# Master.net
KiCad netlist of a schematic drawn in Altium Designer
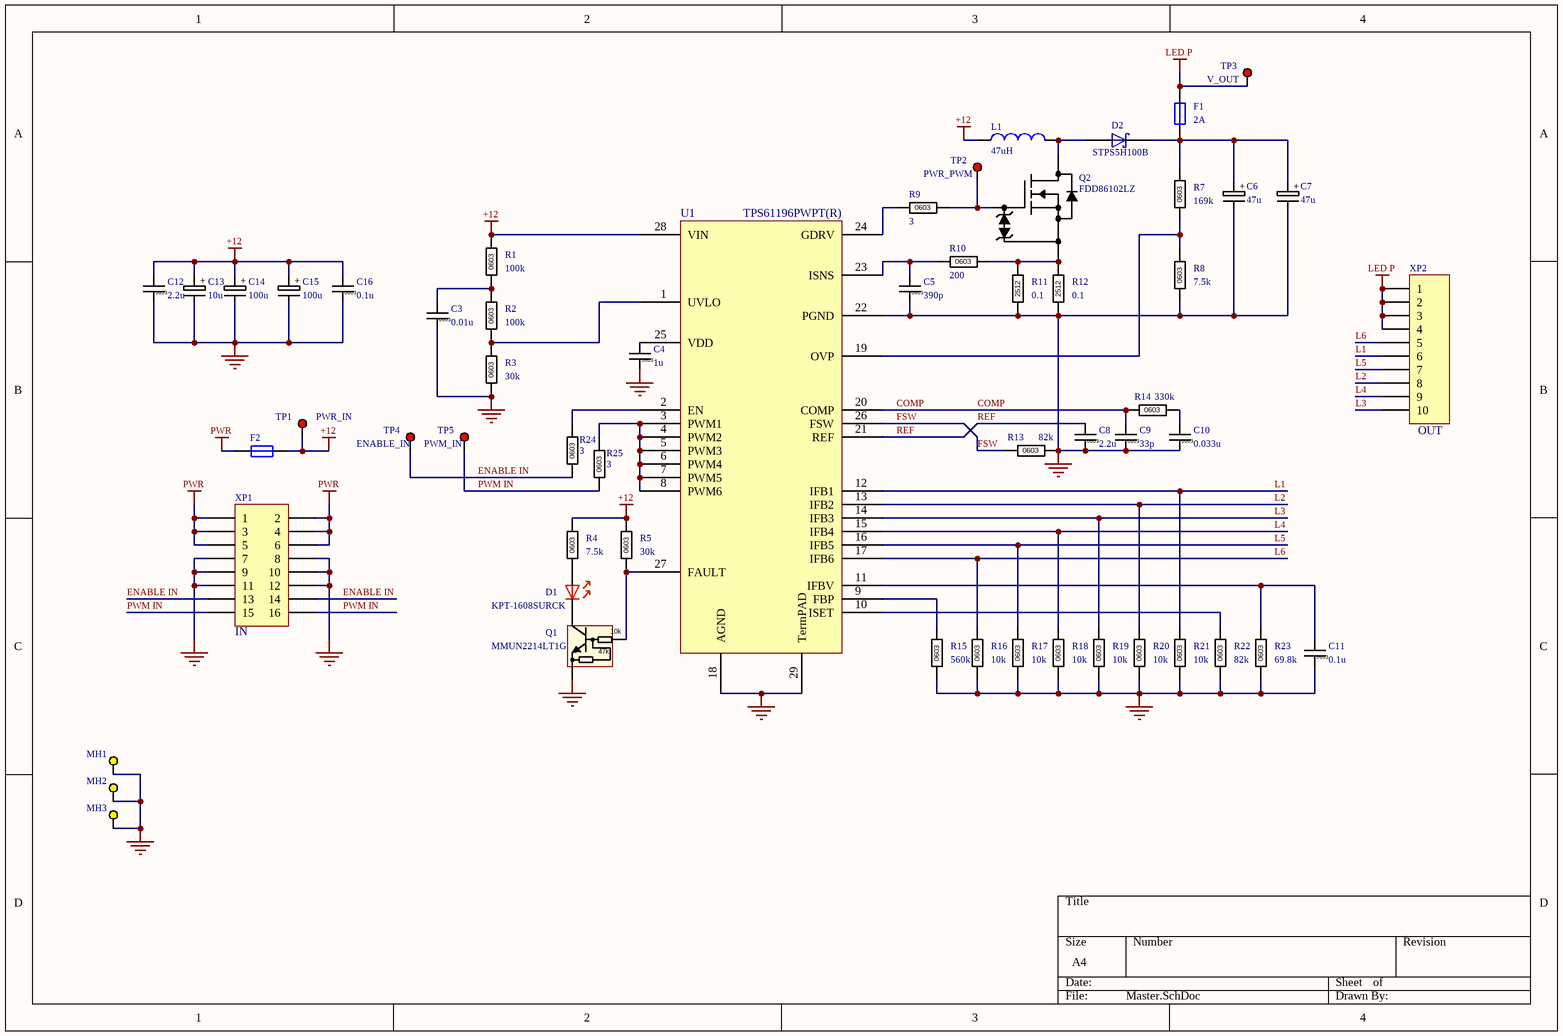
[diagram p0: Master.SchDoc]

(export (version "E")
  (design (tool "Eeschema 10.0.6"))
  (components
    (comp (ref "C3")
      (value "0603-X7R-50-0.01 мкф")
      (footprint "CAP_0603")
      (description "Конденсатор Чип Керамический")
      (fields (field (name "VOLTAGE") "50V") (field (name "CAP") "0.01u") (field (name "FOOT") "0603"))
      (libsource (lib "main") (part "0603-X7R-50-0.01 мкф"))
    )
    (comp (ref "C4")
      (value "0603-X5R-10 1 мкф")
      (footprint "CAP_0603")
      (description "Конденсатор Чип Керамический")
      (fields (field (name "VOLTAGE") "10V") (field (name "CAP") "1u") (field (name "FOOT") "0603"))
      (libsource (lib "main") (part "0603-X5R-10 1 мкф"))
    )
    (comp (ref "C5")
      (value "0603-NP0-50-390 пф J")
      (footprint "CAP_0603")
      (description "Конденсатор Чип Керамический")
      (fields (field (name "VOLTAGE") "50V") (field (name "CAP") "390p") (field (name "FOOT") "0603"))
      (libsource (lib "main") (part "0603-NP0-50-390 пф J"))
    )
    (comp (ref "C6")
      (value "ECAP 47uF 100V 10x12.5")
      (footprint "CAP_ECR 10X12.5")
      (fields (field (name "VOLTAGE") "100V") (field (name "CAP") "47u"))
      (libsource (lib "main") (part "ECAP 47uF 100V 10x12.5"))
    )
    (comp (ref "C7")
      (value "ECAP 47uF 100V 10x12.5")
      (footprint "CAP_ECR 10X12.5")
      (fields (field (name "VOLTAGE") "100V") (field (name "CAP") "47u"))
      (libsource (lib "main") (part "ECAP 47uF 100V 10x12.5"))
    )
    (comp (ref "C8")
      (value "0603-X7R-10 2.2 мкф")
      (footprint "CAP_0603")
      (description "Конденсатор Чип Керамический")
      (fields (field (name "VOLTAGE") "10V") (field (name "CAP") "2.2u") (field (name "FOOT") "0603"))
      (libsource (lib "main") (part "0603-X7R-10 2.2 мкф"))
    )
    (comp (ref "C9")
      (value "0603-NP0-50-33 пф J")
      (footprint "CAP_0603")
      (description "Конденсатор Чип Керамический")
      (fields (field (name "VOLTAGE") "50V") (field (name "CAP") "33p") (field (name "FOOT") "0603"))
      (libsource (lib "main") (part "0603-NP0-50-33 пф J"))
    )
    (comp (ref "C10")
      (value "0603-X7R-50-0.033 мкф")
      (footprint "CAP_0603")
      (description "Конденсатор Чип Керамический")
      (fields (field (name "VOLTAGE") "50V") (field (name "CAP") "0.033u") (field (name "FOOT") "0603"))
      (libsource (lib "main") (part "0603-X7R-50-0.033 мкф"))
    )
    (comp (ref "C11")
      (value "0603-X7R-50-0.1 мкф")
      (footprint "CAP_0603")
      (description "Конденсатор Чип Керамический")
      (fields (field (name "VOLTAGE") "50V") (field (name "CAP") "0.1u") (field (name "FOOT") "0603"))
      (libsource (lib "main") (part "0603-X7R-50-0.1 мкф"))
    )
    (comp (ref "C12")
      (value "0603-X7R-10 2.2 мкф")
      (footprint "CAP_0603")
      (description "Конденсатор Чип Керамический")
      (fields (field (name "VOLTAGE") "10V") (field (name "CAP") "2.2u") (field (name "FOOT") "0603"))
      (libsource (lib "main") (part "0603-X7R-10 2.2 мкф"))
    )
    (comp (ref "C13")
      (value "ESX 50 в-10 мкф 5x11 Hitano")
      (footprint "CAP_ECR 5X11")
      (description "Конденсатор Алюминиевый Низкоимпедансный")
      (fields (field (name "VOLTAGE") "50V") (field (name "CAP") "10u"))
      (libsource (lib "main") (part "ESX 50 в-10 мкф 5x11 Hitano"))
    )
    (comp (ref "C14")
      (value "ECAP (К50-35), 100мкФ, 35В, 105°C, 20%, 6.3x12мм P:2.5мм")
      (footprint "CAP_ECR 5X11")
      (description "Конденсатор электролитический алюминиевый")
      (fields (field (name "VOLTAGE") "50V") (field (name "CAP") "100u"))
      (libsource (lib "main") (part "ECAP 50V 100uF 6.3x12"))
    )
    (comp (ref "C15")
      (value "ECAP (К50-35), 100мкФ, 35В, 105°C, 20%, 6.3x12мм P:2.5мм")
      (footprint "CAP_ECR 5X11")
      (description "Конденсатор электролитический алюминиевый")
      (fields (field (name "VOLTAGE") "50V") (field (name "CAP") "100u"))
      (libsource (lib "main") (part "ECAP 50V 100uF 6.3x12"))
    )
    (comp (ref "C16")
      (value "0603-X7R-50-0.1 мкф")
      (footprint "CAP_0603")
      (description "Конденсатор Чип Керамический")
      (fields (field (name "VOLTAGE") "50V") (field (name "CAP") "0.1u") (field (name "FOOT") "0603"))
      (libsource (lib "main") (part "0603-X7R-50-0.1 мкф"))
    )
    (comp (ref "D1")
      (value "KPT-1608SURCK")
      (footprint "LED_0603_RED")
      (fields
        (field (name "Comment") "KPT-1608SURCK, KingBright")
        (field (name "HELPURL") "L:\\Dev\\Техническая документация\\Светодиоды\\Kingbright\\SMD\\KPT-1608SURCK(0603).pdf")
      )
      (libsource (lib "main") (part "LED_0603_KPT-1608SURCK_red_120mcd"))
    )
    (comp (ref "D2")
      (value "STPS5H100B")
      (footprint "D-PAK")
      (description "DIODE SCHOTTKY 5A 100V")
      (libsource (lib "main") (part "Schottky_STPS5H100B"))
    )
    (comp (ref "F1")
      (value "2A")
      (footprint "FUSE_LITTEL_0154")
      (description "Плавкий предохранитель LITTELFUSE 0154")
      (libsource (lib "main") (part "FUSE_LITTEL 0154"))
    )
    (comp (ref "F2")
      (value "~")
      (footprint "FUSE_LITTEL_0154")
      (description "Плавкий предохранитель LITTELFUSE 0154")
      (libsource (lib "main") (part "FUSE_LITTEL 0154"))
    )
    (comp (ref "L1")
      (value "47uH")
      (footprint "INDUCTOR_B82477G")
      (description "47 мкГн, 2.5 А, 12.8х12.8, Катушка индуктивности SMD")
      (libsource (lib "main") (part "INDUCTOR_B82477G4473M"))
    )
    (comp (ref "MH1")
      (value "MOUNTING HOLE 3MM")
      (footprint "MOUNTING HOLE 3MM")
      (libsource (lib "main") (part "MOUNTING HOLE 3MM"))
    )
    (comp (ref "MH2")
      (value "MOUNTING HOLE 3MM")
      (footprint "MOUNTING HOLE 3MM")
      (libsource (lib "main") (part "MOUNTING HOLE 3MM"))
    )
    (comp (ref "MH3")
      (value "MOUNTING HOLE 3MM")
      (footprint "MOUNTING HOLE 3MM")
      (libsource (lib "main") (part "MOUNTING HOLE 3MM"))
    )
    (comp (ref "Q1")
      (value "MMUN2214LT1G")
      (footprint "SOT_23")
      (description "NPN Digital Transistor")
      (fields (field (name "PUBLISHER") "Altium Limited"))
      (libsource (lib "main") (part "BEC_MMUN2214LT1G_50V 0.1A 0.25W"))
    )
    (comp (ref "Q2")
      (value "FDD86102LZ")
      (footprint "D-PAK")
      (description "MOSFET N-CHANNEL 100V 8A")
      (libsource (lib "main") (part "MOSFET_FDD86102LZ"))
    )
    (comp (ref "R1")
      (value "100k")
      (footprint "resistor_0603")
      (description "Резистор Чип")
      (fields
        (field (name "POWER") "0.1W")
        (field (name "FOOT") "0603")
        (field (name "Comment") "0603-100к J")
      )
      (libsource (lib "main") (part "0603-100 к J"))
    )
    (comp (ref "R2")
      (value "100k")
      (footprint "resistor_0603")
      (description "Резистор Чип")
      (fields
        (field (name "POWER") "0.1W")
        (field (name "FOOT") "0603")
        (field (name "Comment") "0603-100к J")
      )
      (libsource (lib "main") (part "0603-100 к J"))
    )
    (comp (ref "R3")
      (value "30k")
      (footprint "resistor_0603")
      (description "Резистор Чип")
      (fields (field (name "POWER") "0.1W") (field (name "TOLERANCE") "1%") (field (name "FOOT") "0603"))
      (libsource (lib "main") (part "0603-30 к F"))
    )
    (comp (ref "R4")
      (value "7.5k")
      (footprint "resistor_0603")
      (description "Резистор Чип")
      (fields (field (name "POWER") "0.1W") (field (name "TOLERANCE") "1%") (field (name "FOOT") "0603"))
      (libsource (lib "main") (part "0603-7.5 к F"))
    )
    (comp (ref "R5")
      (value "30k")
      (footprint "resistor_0603")
      (description "Резистор Чип")
      (fields (field (name "POWER") "0.1W") (field (name "TOLERANCE") "1%") (field (name "FOOT") "0603"))
      (libsource (lib "main") (part "0603-30 к F"))
    )
    (comp (ref "R7")
      (value "169k")
      (footprint "resistor_0603")
      (description "Резистор Чип")
      (fields (field (name "POWER") "0.1W") (field (name "TOLERANCE") "1%") (field (name "FOOT") "0603"))
      (libsource (lib "main") (part "0603-169 к F"))
    )
    (comp (ref "R8")
      (value "7.5k")
      (footprint "resistor_0603")
      (description "Резистор Чип")
      (fields (field (name "POWER") "0.1W") (field (name "TOLERANCE") "1%") (field (name "FOOT") "0603"))
      (libsource (lib "main") (part "0603-7.5 к F"))
    )
    (comp (ref "R9")
      (value "3")
      (footprint "resistor_0603")
      (description "Резистор Чип")
      (fields (field (name "POWER") "0.1W") (field (name "TOLERANCE") "1%") (field (name "FOOT") "0603"))
      (libsource (lib "main") (part "0603-3 F"))
    )
    (comp (ref "R10")
      (value "200")
      (footprint "resistor_0603")
      (description "Резистор Чип")
      (fields (field (name "POWER") "0.1W") (field (name "TOLERANCE") "1%") (field (name "FOOT") "0603"))
      (libsource (lib "main") (part "0603-200 F"))
    )
    (comp (ref "R11")
      (value "0.1")
      (footprint "resistor_2512")
      (description "Резистор Чип")
      (fields (field (name "POWER") "1W") (field (name "FOOT") "2512") (field (name "Comment") "2512-0.1 F"))
      (libsource (lib "main") (part "2512-0.1 F"))
    )
    (comp (ref "R12")
      (value "0.1")
      (footprint "resistor_2512")
      (description "Резистор Чип")
      (fields (field (name "POWER") "1W") (field (name "FOOT") "2512") (field (name "Comment") "2512-0.1 F"))
      (libsource (lib "main") (part "2512-0.1 F"))
    )
    (comp (ref "R13")
      (value "82k")
      (footprint "resistor_0603")
      (description "Резистор Чип")
      (fields
        (field (name "POWER") "0.1W")
        (field (name "FOOT") "0603")
        (field (name "Comment") "0603-82 к J")
      )
      (libsource (lib "main") (part "0603-82 к J"))
    )
    (comp (ref "R14")
      (value "330k")
      (footprint "resistor_0603")
      (description "Резистор Чип")
      (fields
        (field (name "POWER") "0.1W")
        (field (name "FOOT") "0603")
        (field (name "Comment") "0603-330 J")
      )
      (libsource (lib "main") (part "0603-330 J"))
    )
    (comp (ref "R15")
      (value "560k")
      (footprint "resistor_0603")
      (description "Резистор Чип")
      (fields (field (name "POWER") "0.1W") (field (name "TOLERANCE") "1%") (field (name "FOOT") "0603"))
      (libsource (lib "main") (part "0603-560 к F"))
    )
    (comp (ref "R16")
      (value "10k")
      (footprint "resistor_0603")
      (description "Резистор Чип")
      (fields
        (field (name "POWER") "0.1W")
        (field (name "FOOT") "0603")
        (field (name "Comment") "0603-10к J")
      )
      (libsource (lib "main") (part "0603-10 к J"))
    )
    (comp (ref "R17")
      (value "10k")
      (footprint "resistor_0603")
      (description "Резистор Чип")
      (fields
        (field (name "POWER") "0.1W")
        (field (name "FOOT") "0603")
        (field (name "Comment") "0603-10к J")
      )
      (libsource (lib "main") (part "0603-10 к J"))
    )
    (comp (ref "R18")
      (value "10k")
      (footprint "resistor_0603")
      (description "Резистор Чип")
      (fields
        (field (name "POWER") "0.1W")
        (field (name "FOOT") "0603")
        (field (name "Comment") "0603-10к J")
      )
      (libsource (lib "main") (part "0603-10 к J"))
    )
    (comp (ref "R19")
      (value "10k")
      (footprint "resistor_0603")
      (description "Резистор Чип")
      (fields
        (field (name "POWER") "0.1W")
        (field (name "FOOT") "0603")
        (field (name "Comment") "0603-10к J")
      )
      (libsource (lib "main") (part "0603-10 к J"))
    )
    (comp (ref "R20")
      (value "10k")
      (footprint "resistor_0603")
      (description "Резистор Чип")
      (fields
        (field (name "POWER") "0.1W")
        (field (name "FOOT") "0603")
        (field (name "Comment") "0603-10к J")
      )
      (libsource (lib "main") (part "0603-10 к J"))
    )
    (comp (ref "R21")
      (value "10k")
      (footprint "resistor_0603")
      (description "Резистор Чип")
      (fields
        (field (name "POWER") "0.1W")
        (field (name "FOOT") "0603")
        (field (name "Comment") "0603-10к J")
      )
      (libsource (lib "main") (part "0603-10 к J"))
    )
    (comp (ref "R22")
      (value "82k")
      (footprint "resistor_0603")
      (description "Резистор Чип")
      (fields
        (field (name "POWER") "0.1W")
        (field (name "FOOT") "0603")
        (field (name "Comment") "0603-82 к J")
      )
      (libsource (lib "main") (part "0603-82 к J"))
    )
    (comp (ref "R23")
      (value "69.8k")
      (footprint "resistor_0603")
      (description "Резистор Чип")
      (fields (field (name "POWER") "0.1W") (field (name "TOLERANCE") "1%") (field (name "FOOT") "0603"))
      (libsource (lib "main") (part "0603-69.8 к F"))
    )
    (comp (ref "R24")
      (value "3")
      (footprint "resistor_0603")
      (description "Резистор Чип")
      (fields (field (name "POWER") "0.1W") (field (name "TOLERANCE") "1%") (field (name "FOOT") "0603"))
      (libsource (lib "main") (part "0603-3 F"))
    )
    (comp (ref "R25")
      (value "3")
      (footprint "resistor_0603")
      (description "Резистор Чип")
      (fields (field (name "POWER") "0.1W") (field (name "TOLERANCE") "1%") (field (name "FOOT") "0603"))
      (libsource (lib "main") (part "0603-3 F"))
    )
    (comp (ref "TP1")
      (value "PWR_IN")
      (footprint "OTHER_SMD_TP_1.5MM")
      (libsource (lib "main") (part "Test Point_1.5MM"))
    )
    (comp (ref "TP2")
      (value "PWR_PWM")
      (footprint "OTHER_SMD_TP_1.5MM")
      (libsource (lib "main") (part "Test Point_1.5MM"))
    )
    (comp (ref "TP3")
      (value "V_OUT")
      (footprint "OTHER_SMD_TP_1.5MM")
      (libsource (lib "main") (part "Test Point_1.5MM"))
    )
    (comp (ref "TP4")
      (value "ENABLE_IN")
      (footprint "OTHER_SMD_TP_1.5MM")
      (libsource (lib "main") (part "Test Point_1.5MM"))
    )
    (comp (ref "TP5")
      (value "PWM_IN")
      (footprint "OTHER_SMD_TP_1.5MM")
      (libsource (lib "main") (part "Test Point_1.5MM"))
    )
    (comp (ref "U1")
      (value "TPS61196PWPT(R)")
      (footprint "HTSSOP_28")
      (libsource (lib "main") (part "LED DRV_TPS61196"))
    )
    (comp (ref "XP1")
      (value "IN")
      (footprint "CONN_PBD-16 RA")
      (description "Header, 8-Pin, Dual row")
      (fields (field (name "PUBLISHER") "Altium Limited"))
      (libsource (lib "main") (part "CONN_PBD-16 RA"))
    )
    (comp (ref "XP2")
      (value "OUT")
      (footprint "CONN_IDC-10")
      (description "Header, 10-Pin")
      (fields (field (name "PUBLISHER") "Altium Limited"))
      (libsource (lib "main") (part "CONN_IDC-10 (Single Row)"))
    )
  )
  (nets
    (net (code "1") (name "+12") (class "Default")
      (node (ref "C12") (pin "1") (pinfunction "1_1") (pintype "passive"))
      (node (ref "C13") (pin "1") (pinfunction "1_1") (pintype "passive"))
      (node (ref "C14") (pin "1") (pinfunction "1_1") (pintype "passive"))
      (node (ref "C15") (pin "1") (pinfunction "1_1") (pintype "passive"))
      (node (ref "C16") (pin "1") (pinfunction "1_1") (pintype "passive"))
      (node (ref "F2") (pin "1") (pinfunction "1_1") (pintype "passive"))
      (node (ref "L1") (pin "1") (pinfunction "1_1") (pintype "passive"))
      (node (ref "R1") (pin "2") (pinfunction "2_2") (pintype "passive"))
      (node (ref "R4") (pin "2") (pinfunction "2_2") (pintype "passive"))
      (node (ref "R5") (pin "2") (pinfunction "2_2") (pintype "passive"))
      (node (ref "TP1") (pin "1") (pinfunction "1_1") (pintype "passive"))
      (node (ref "U1") (pin "28") (pinfunction "VIN_28") (pintype "passive"))
    )
    (net (code "2") (name "/COMP") (class "Default")
      (node (ref "C9") (pin "1") (pinfunction "1_1") (pintype "passive"))
      (node (ref "R14") (pin "2") (pinfunction "2_2") (pintype "passive"))
      (node (ref "U1") (pin "20") (pinfunction "COMP_20") (pintype "passive"))
    )
    (net (code "3") (name "/ENABLE IN") (class "Default")
      (node (ref "R24") (pin "1") (pinfunction "1_1") (pintype "passive"))
      (node (ref "TP4") (pin "1") (pinfunction "1_1") (pintype "passive"))
      (node (ref "XP1") (pin "13") (pinfunction "13_13") (pintype "passive"))
      (node (ref "XP1") (pin "14") (pinfunction "14_14") (pintype "passive"))
    )
    (net (code "4") (name "/FSW") (class "Default")
      (node (ref "R13") (pin "1") (pinfunction "1_1") (pintype "passive"))
      (node (ref "U1") (pin "26") (pinfunction "FSW_26") (pintype "passive"))
    )
    (net (code "5") (name "/L1") (class "Default")
      (node (ref "R21") (pin "2") (pinfunction "2_2") (pintype "passive"))
      (node (ref "U1") (pin "12") (pinfunction "IFB1_12") (pintype "passive"))
      (node (ref "XP2") (pin "6") (pinfunction "6_6") (pintype "passive"))
    )
    (net (code "6") (name "/L2") (class "Default")
      (node (ref "R20") (pin "2") (pinfunction "2_2") (pintype "passive"))
      (node (ref "U1") (pin "13") (pinfunction "IFB2_13") (pintype "passive"))
      (node (ref "XP2") (pin "8") (pinfunction "8_8") (pintype "passive"))
    )
    (net (code "7") (name "/L3") (class "Default")
      (node (ref "R19") (pin "2") (pinfunction "2_2") (pintype "passive"))
      (node (ref "U1") (pin "14") (pinfunction "IFB3_14") (pintype "passive"))
      (node (ref "XP2") (pin "10") (pinfunction "10_10") (pintype "passive"))
    )
    (net (code "8") (name "/L4") (class "Default")
      (node (ref "R18") (pin "2") (pinfunction "2_2") (pintype "passive"))
      (node (ref "U1") (pin "15") (pinfunction "IFB4_15") (pintype "passive"))
      (node (ref "XP2") (pin "9") (pinfunction "9_9") (pintype "passive"))
    )
    (net (code "9") (name "/L5") (class "Default")
      (node (ref "R17") (pin "2") (pinfunction "2_2") (pintype "passive"))
      (node (ref "U1") (pin "16") (pinfunction "IFB5_16") (pintype "passive"))
      (node (ref "XP2") (pin "7") (pinfunction "7_7") (pintype "passive"))
    )
    (net (code "10") (name "/L6") (class "Default")
      (node (ref "R16") (pin "2") (pinfunction "2_2") (pintype "passive"))
      (node (ref "U1") (pin "17") (pinfunction "IFB6_17") (pintype "passive"))
      (node (ref "XP2") (pin "5") (pinfunction "5_5") (pintype "passive"))
    )
    (net (code "11") (name "/PWM IN") (class "Default")
      (node (ref "R25") (pin "1") (pinfunction "1_1") (pintype "passive"))
      (node (ref "TP5") (pin "1") (pinfunction "1_1") (pintype "passive"))
      (node (ref "XP1") (pin "15") (pinfunction "15_15") (pintype "passive"))
      (node (ref "XP1") (pin "16") (pinfunction "16_16") (pintype "passive"))
    )
    (net (code "12") (name "/REF") (class "Default")
      (node (ref "C8") (pin "1") (pinfunction "1_1") (pintype "passive"))
      (node (ref "U1") (pin "21") (pinfunction "REF_21") (pintype "passive"))
    )
    (net (code "13") (name "GND") (class "Default")
      (node (ref "C10") (pin "2") (pinfunction "2_2") (pintype "passive"))
      (node (ref "C11") (pin "2") (pinfunction "2_2") (pintype "passive"))
      (node (ref "C12") (pin "2") (pinfunction "2_2") (pintype "passive"))
      (node (ref "C13") (pin "2") (pinfunction "2_2") (pintype "passive"))
      (node (ref "C14") (pin "2") (pinfunction "2_2") (pintype "passive"))
      (node (ref "C15") (pin "2") (pinfunction "2_2") (pintype "passive"))
      (node (ref "C16") (pin "2") (pinfunction "2_2") (pintype "passive"))
      (node (ref "C3") (pin "2") (pinfunction "2_2") (pintype "passive"))
      (node (ref "C4") (pin "2") (pinfunction "2_2") (pintype "passive"))
      (node (ref "C5") (pin "2") (pinfunction "2_2") (pintype "passive"))
      (node (ref "C6") (pin "2") (pinfunction "2_2") (pintype "passive"))
      (node (ref "C7") (pin "2") (pinfunction "2_2") (pintype "passive"))
      (node (ref "C8") (pin "2") (pinfunction "2_2") (pintype "passive"))
      (node (ref "C9") (pin "2") (pinfunction "2_2") (pintype "passive"))
      (node (ref "MH1") (pin "0") (pinfunction "0_0") (pintype "passive"))
      (node (ref "MH2") (pin "0") (pinfunction "0_0") (pintype "passive"))
      (node (ref "MH3") (pin "0") (pinfunction "0_0") (pintype "passive"))
      (node (ref "Q1") (pin "2") (pinfunction "E_2") (pintype "passive"))
      (node (ref "R11") (pin "1") (pinfunction "1_1") (pintype "passive"))
      (node (ref "R12") (pin "1") (pinfunction "1_1") (pintype "passive"))
      (node (ref "R13") (pin "2") (pinfunction "2_2") (pintype "passive"))
      (node (ref "R15") (pin "1") (pinfunction "1_1") (pintype "passive"))
      (node (ref "R16") (pin "1") (pinfunction "1_1") (pintype "passive"))
      (node (ref "R17") (pin "1") (pinfunction "1_1") (pintype "passive"))
      (node (ref "R18") (pin "1") (pinfunction "1_1") (pintype "passive"))
      (node (ref "R19") (pin "1") (pinfunction "1_1") (pintype "passive"))
      (node (ref "R20") (pin "1") (pinfunction "1_1") (pintype "passive"))
      (node (ref "R21") (pin "1") (pinfunction "1_1") (pintype "passive"))
      (node (ref "R22") (pin "1") (pinfunction "1_1") (pintype "passive"))
      (node (ref "R23") (pin "1") (pinfunction "1_1") (pintype "passive"))
      (node (ref "R3") (pin "1") (pinfunction "1_1") (pintype "passive"))
      (node (ref "R8") (pin "1") (pinfunction "1_1") (pintype "passive"))
      (node (ref "U1") (pin "18") (pinfunction "AGND_18") (pintype "passive"))
      (node (ref "U1") (pin "22") (pinfunction "PGND_22") (pintype "passive"))
      (node (ref "U1") (pin "29") (pinfunction "TermPAD_29") (pintype "passive"))
      (node (ref "XP1") (pin "10") (pinfunction "10_10") (pintype "passive"))
      (node (ref "XP1") (pin "11") (pinfunction "11_11") (pintype "passive"))
      (node (ref "XP1") (pin "12") (pinfunction "12_12") (pintype "passive"))
      (node (ref "XP1") (pin "7") (pinfunction "7_7") (pintype "passive"))
      (node (ref "XP1") (pin "8") (pinfunction "8_8") (pintype "passive"))
      (node (ref "XP1") (pin "9") (pinfunction "9_9") (pintype "passive"))
    )
    (net (code "14") (name "LED P") (class "Default")
      (node (ref "F1") (pin "2") (pinfunction "2_2") (pintype "passive"))
      (node (ref "TP3") (pin "1") (pinfunction "1_1") (pintype "passive"))
      (node (ref "XP2") (pin "1") (pinfunction "1_1") (pintype "passive"))
      (node (ref "XP2") (pin "2") (pinfunction "2_2") (pintype "passive"))
      (node (ref "XP2") (pin "3") (pinfunction "3_3") (pintype "passive"))
      (node (ref "XP2") (pin "4") (pinfunction "4_4") (pintype "passive"))
    )
    (net (code "15") (name "Net-(C3-Pad1)") (class "Default")
      (node (ref "C3") (pin "1") (pinfunction "1_1") (pintype "passive"))
      (node (ref "R1") (pin "1") (pinfunction "1_1") (pintype "passive"))
      (node (ref "R2") (pin "2") (pinfunction "2_2") (pintype "passive"))
    )
    (net (code "16") (name "Net-(C10-Pad1)") (class "Default")
      (node (ref "C10") (pin "1") (pinfunction "1_1") (pintype "passive"))
      (node (ref "R14") (pin "1") (pinfunction "1_1") (pintype "passive"))
    )
    (net (code "17") (name "Net-(D1-Pad1)") (class "Default")
      (node (ref "D1") (pin "1") (pinfunction "1_1") (pintype "passive"))
      (node (ref "R4") (pin "1") (pinfunction "1_1") (pintype "passive"))
    )
    (net (code "18") (name "Net-(D2-A)") (class "Default")
      (node (ref "D2") (pin "2") (pinfunction "A_2") (pintype "passive"))
      (node (ref "L1") (pin "2") (pinfunction "2_2") (pintype "passive"))
      (node (ref "Q2") (pin "3") (pinfunction "D_3") (pintype "passive"))
    )
    (net (code "19") (name "Net-(D2-K)") (class "Default")
      (node (ref "C6") (pin "1") (pinfunction "1_1") (pintype "passive"))
      (node (ref "C7") (pin "1") (pinfunction "1_1") (pintype "passive"))
      (node (ref "D2") (pin "3") (pinfunction "K_3") (pintype "passive"))
      (node (ref "F1") (pin "1") (pinfunction "1_1") (pintype "passive"))
      (node (ref "R7") (pin "2") (pinfunction "2_2") (pintype "passive"))
    )
    (net (code "20") (name "Net-(Q1-B)") (class "Default")
      (node (ref "Q1") (pin "1") (pinfunction "B_1") (pintype "passive"))
      (node (ref "R5") (pin "1") (pinfunction "1_1") (pintype "passive"))
      (node (ref "U1") (pin "27") (pinfunction "FAULT_27") (pintype "passive"))
    )
    (net (code "21") (name "Net-(Q1-C)") (class "Default")
      (node (ref "D1") (pin "2") (pinfunction "2_2") (pintype "passive"))
      (node (ref "Q1") (pin "3") (pinfunction "C_3") (pintype "passive"))
    )
    (net (code "22") (name "Net-(Q2-G)") (class "Default")
      (node (ref "Q2") (pin "1") (pinfunction "G_1") (pintype "passive"))
      (node (ref "R9") (pin "2") (pinfunction "2_2") (pintype "passive"))
      (node (ref "TP2") (pin "1") (pinfunction "1_1") (pintype "passive"))
    )
    (net (code "23") (name "Net-(Q2-S)") (class "Default")
      (node (ref "Q2") (pin "2") (pinfunction "S_2") (pintype "passive"))
      (node (ref "R10") (pin "2") (pinfunction "2_2") (pintype "passive"))
      (node (ref "R11") (pin "2") (pinfunction "2_2") (pintype "passive"))
      (node (ref "R12") (pin "2") (pinfunction "2_2") (pintype "passive"))
    )
    (net (code "24") (name "Net-(U1-EN)") (class "Default")
      (node (ref "R24") (pin "2") (pinfunction "2_2") (pintype "passive"))
      (node (ref "U1") (pin "2") (pinfunction "EN_2") (pintype "passive"))
    )
    (net (code "25") (name "Net-(U1-FBP)") (class "Default")
      (node (ref "R15") (pin "2") (pinfunction "2_2") (pintype "passive"))
      (node (ref "U1") (pin "9") (pinfunction "FBP_9") (pintype "passive"))
    )
    (net (code "26") (name "Net-(U1-GDRV)") (class "Default")
      (node (ref "R9") (pin "1") (pinfunction "1_1") (pintype "passive"))
      (node (ref "U1") (pin "24") (pinfunction "GDRV_24") (pintype "passive"))
    )
    (net (code "27") (name "Net-(U1-IFBV)") (class "Default")
      (node (ref "C11") (pin "1") (pinfunction "1_1") (pintype "passive"))
      (node (ref "R23") (pin "2") (pinfunction "2_2") (pintype "passive"))
      (node (ref "U1") (pin "11") (pinfunction "IFBV_11") (pintype "passive"))
    )
    (net (code "28") (name "Net-(U1-ISET)") (class "Default")
      (node (ref "R22") (pin "2") (pinfunction "2_2") (pintype "passive"))
      (node (ref "U1") (pin "10") (pinfunction "ISET_10") (pintype "passive"))
    )
    (net (code "29") (name "Net-(U1-ISNS)") (class "Default")
      (node (ref "C5") (pin "1") (pinfunction "1_1") (pintype "passive"))
      (node (ref "R10") (pin "1") (pinfunction "1_1") (pintype "passive"))
      (node (ref "U1") (pin "23") (pinfunction "ISNS_23") (pintype "passive"))
    )
    (net (code "30") (name "Net-(U1-OVP)") (class "Default")
      (node (ref "R7") (pin "1") (pinfunction "1_1") (pintype "passive"))
      (node (ref "R8") (pin "2") (pinfunction "2_2") (pintype "passive"))
      (node (ref "U1") (pin "19") (pinfunction "OVP_19") (pintype "passive"))
    )
    (net (code "31") (name "Net-(U1-PWM1)") (class "Default")
      (node (ref "R25") (pin "2") (pinfunction "2_2") (pintype "passive"))
      (node (ref "U1") (pin "3") (pinfunction "PWM1_3") (pintype "passive"))
      (node (ref "U1") (pin "4") (pinfunction "PWM2_4") (pintype "passive"))
      (node (ref "U1") (pin "5") (pinfunction "PWM3_5") (pintype "passive"))
      (node (ref "U1") (pin "6") (pinfunction "PWM4_6") (pintype "passive"))
      (node (ref "U1") (pin "7") (pinfunction "PWM5_7") (pintype "passive"))
      (node (ref "U1") (pin "8") (pinfunction "PWM6_8") (pintype "passive"))
    )
    (net (code "32") (name "Net-(U1-UVLO)") (class "Default")
      (node (ref "R2") (pin "1") (pinfunction "1_1") (pintype "passive"))
      (node (ref "R3") (pin "2") (pinfunction "2_2") (pintype "passive"))
      (node (ref "U1") (pin "1") (pinfunction "UVLO_1") (pintype "passive"))
    )
    (net (code "33") (name "Net-(U1-VDD)") (class "Default")
      (node (ref "C4") (pin "1") (pinfunction "1_1") (pintype "passive"))
      (node (ref "U1") (pin "25") (pinfunction "VDD_25") (pintype "passive"))
    )
    (net (code "34") (name "PWR") (class "Default")
      (node (ref "F2") (pin "2") (pinfunction "2_2") (pintype "passive"))
      (node (ref "XP1") (pin "1") (pinfunction "1_1") (pintype "passive"))
      (node (ref "XP1") (pin "2") (pinfunction "2_2") (pintype "passive"))
      (node (ref "XP1") (pin "3") (pinfunction "3_3") (pintype "passive"))
      (node (ref "XP1") (pin "4") (pinfunction "4_4") (pintype "passive"))
      (node (ref "XP1") (pin "5") (pinfunction "5_5") (pintype "passive"))
      (node (ref "XP1") (pin "6") (pinfunction "6_6") (pintype "passive"))
    )
  )
)
